# XBeeModule.net
KiCad netlist of a schematic drawn in Altium Designer
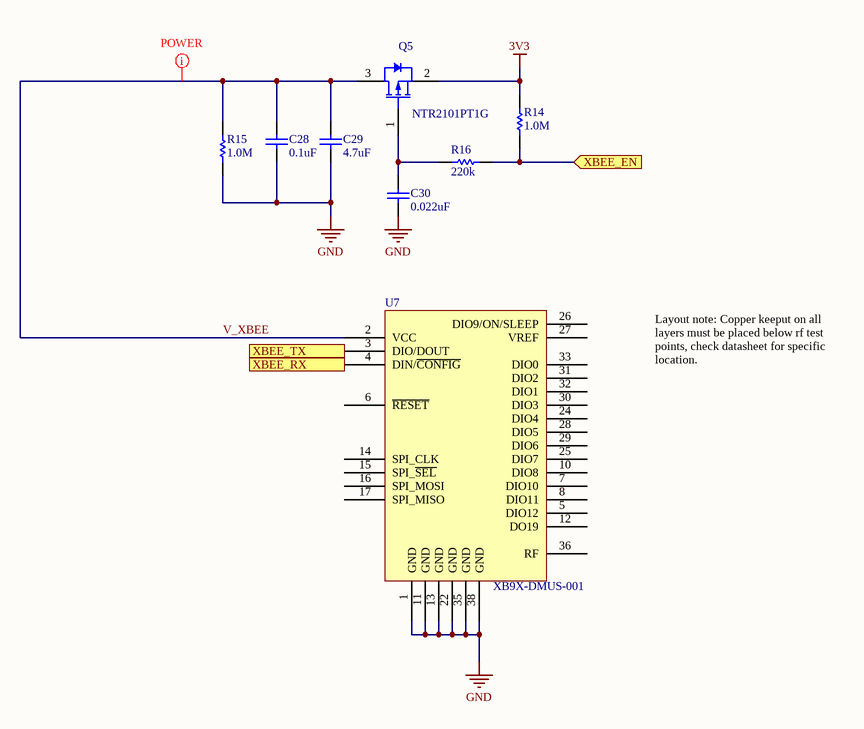
[diagram p0: XBeeModule.SchDoc]

(export (version "E")
  (design (tool "Eeschema 10.0.6"))
  (components
    (comp (ref "C28")
      (value "0.1uF")
      (footprint "0402cap")
      (description "0402 Ceramic Chip Capacitor - Standard")
      (fields (field (name "Comment") "C0402"))
      (libsource (lib "lib-Standard") (part "C0402"))
    )
    (comp (ref "C29")
      (value "4.7uF")
      (footprint "0603CAP")
      (description "0603 Ceramic Chip Capacitor - Standard")
      (fields (field (name "Comment") "C0603"))
      (libsource (lib "lib-Standard") (part "C0603"))
    )
    (comp (ref "C30")
      (value "0.022uF")
      (footprint "0402cap")
      (description "0402 Ceramic Chip Capacitor - Standard")
      (fields (field (name "Comment") "C0402"))
      (libsource (lib "lib-Standard") (part "C0402"))
    )
    (comp (ref "Q5")
      (value "NTR2101PT1G")
      (footprint "ONSC-SOT-23-3-318-08_V")
      (description "Small Signal MOSFET, -8 V, -3.7 A, Single P-Channel, 3-Pin SOT-23, Pb-Free, Tape and Reel")
      (libsource (lib "ON Semi MOSFETs") (part "NTR2101PT1G"))
    )
    (comp (ref "R14")
      (value "1.0M")
      (footprint "0402RES")
      (description "0402 Chip Resistor - Standard")
      (fields (field (name "Comment") "R0402"))
      (libsource (lib "lib-Standard") (part "R0402"))
    )
    (comp (ref "R15")
      (value "1.0M")
      (footprint "0402RES")
      (description "0402 Chip Resistor - Standard")
      (fields (field (name "Comment") "R0402"))
      (libsource (lib "lib-Standard") (part "R0402"))
    )
    (comp (ref "R16")
      (value "220k")
      (footprint "0402RES")
      (description "0402 Chip Resistor - Standard")
      (fields (field (name "Comment") "R0402"))
      (libsource (lib "lib-Standard") (part "R0402"))
    )
    (comp (ref "U7")
      (value "XB9X-DMUS-001")
      (footprint "XBee/XBee-PRO")
      (libsource (lib "lib-IC_RF") (part "XB9X-DMUS-001"))
    )
  )
  (nets
    (net (code "1") (name "/V_XBEE") (class "Default")
      (node (ref "C28") (pin "2") (pinfunction "2_2") (pintype "passive"))
      (node (ref "C29") (pin "2") (pinfunction "2_2") (pintype "passive"))
      (node (ref "Q5") (pin "3") (pinfunction "D_3") (pintype "passive"))
      (node (ref "R15") (pin "2") (pinfunction "2_2") (pintype "passive"))
      (node (ref "U7") (pin "2") (pinfunction "VCC_2") (pintype "passive"))
    )
    (net (code "2") (name "/XBEE_EN") (class "Default")
      (node (ref "R14") (pin "1") (pinfunction "1_1") (pintype "passive"))
      (node (ref "R16") (pin "2") (pinfunction "2_2") (pintype "passive"))
    )
    (net (code "3") (name "/XBEE_RX") (class "Default")
      (node (ref "U7") (pin "4") (pinfunction "DIN/~{CONFIG}_4") (pintype "passive"))
    )
    (net (code "4") (name "/XBEE_TX") (class "Default")
      (node (ref "U7") (pin "3") (pinfunction "DIO/DOUT_3") (pintype "passive"))
    )
    (net (code "5") (name "3V3") (class "Default")
      (node (ref "Q5") (pin "2") (pinfunction "S_2") (pintype "passive"))
      (node (ref "R14") (pin "2") (pinfunction "2_2") (pintype "passive"))
    )
    (net (code "6") (name "GND") (class "Default")
      (node (ref "C28") (pin "1") (pinfunction "1_1") (pintype "passive"))
      (node (ref "C29") (pin "1") (pinfunction "1_1") (pintype "passive"))
      (node (ref "C30") (pin "1") (pinfunction "1_1") (pintype "passive"))
      (node (ref "R15") (pin "1") (pinfunction "1_1") (pintype "passive"))
      (node (ref "U7") (pin "1") (pinfunction "GND_1") (pintype "passive"))
      (node (ref "U7") (pin "11") (pinfunction "GND_11") (pintype "passive"))
      (node (ref "U7") (pin "13") (pinfunction "GND_13") (pintype "passive"))
      (node (ref "U7") (pin "22") (pinfunction "GND_22") (pintype "passive"))
      (node (ref "U7") (pin "35") (pinfunction "GND_35") (pintype "passive"))
      (node (ref "U7") (pin "38") (pinfunction "GND_38") (pintype "passive"))
    )
    (net (code "7") (name "Net-(Q5-G)") (class "Default")
      (node (ref "C30") (pin "2") (pinfunction "2_2") (pintype "passive"))
      (node (ref "Q5") (pin "1") (pinfunction "G_1") (pintype "passive"))
      (node (ref "R16") (pin "1") (pinfunction "1_1") (pintype "passive"))
    )
    (net (code "8") (name "unconnected-(U7-DIO0-Pad33)") (class "Default")
      (node (ref "U7") (pin "33") (pinfunction "DIO0_33") (pintype "passive"))
    )
    (net (code "9") (name "unconnected-(U7-DIO1-Pad32)") (class "Default")
      (node (ref "U7") (pin "32") (pinfunction "DIO1_32") (pintype "passive"))
    )
    (net (code "10") (name "unconnected-(U7-DIO2-Pad31)") (class "Default")
      (node (ref "U7") (pin "31") (pinfunction "DIO2_31") (pintype "passive"))
    )
    (net (code "11") (name "unconnected-(U7-DIO3-Pad30)") (class "Default")
      (node (ref "U7") (pin "30") (pinfunction "DIO3_30") (pintype "passive"))
    )
    (net (code "12") (name "unconnected-(U7-DIO4-Pad24)") (class "Default")
      (node (ref "U7") (pin "24") (pinfunction "DIO4_24") (pintype "passive"))
    )
    (net (code "13") (name "unconnected-(U7-DIO5-Pad28)") (class "Default")
      (node (ref "U7") (pin "28") (pinfunction "DIO5_28") (pintype "passive"))
    )
    (net (code "14") (name "unconnected-(U7-DIO6-Pad29)") (class "Default")
      (node (ref "U7") (pin "29") (pinfunction "DIO6_29") (pintype "passive"))
    )
    (net (code "15") (name "unconnected-(U7-DIO7-Pad25)") (class "Default")
      (node (ref "U7") (pin "25") (pinfunction "DIO7_25") (pintype "passive"))
    )
    (net (code "16") (name "unconnected-(U7-DIO8-Pad10)") (class "Default")
      (node (ref "U7") (pin "10") (pinfunction "DIO8_10") (pintype "passive"))
    )
    (net (code "17") (name "unconnected-(U7-DIO9{slash}ON{slash}SLEEP-Pad26)") (class "Default")
      (node (ref "U7") (pin "26") (pinfunction "DIO9/ON/SLEEP_26") (pintype "passive"))
    )
    (net (code "18") (name "unconnected-(U7-DIO10-Pad7)") (class "Default")
      (node (ref "U7") (pin "7") (pinfunction "DIO10_7") (pintype "passive"))
    )
    (net (code "19") (name "unconnected-(U7-DIO11-Pad8)") (class "Default")
      (node (ref "U7") (pin "8") (pinfunction "DIO11_8") (pintype "passive"))
    )
    (net (code "20") (name "unconnected-(U7-DIO12-Pad5)") (class "Default")
      (node (ref "U7") (pin "5") (pinfunction "DIO12_5") (pintype "passive"))
    )
    (net (code "21") (name "unconnected-(U7-DO19-Pad12)") (class "Default")
      (node (ref "U7") (pin "12") (pinfunction "DO19_12") (pintype "passive"))
    )
    (net (code "22") (name "unconnected-(U7-RF-Pad36)") (class "Default")
      (node (ref "U7") (pin "36") (pinfunction "RF_36") (pintype "passive"))
    )
    (net (code "23") (name "unconnected-(U7-SPI_CLK-Pad14)") (class "Default")
      (node (ref "U7") (pin "14") (pinfunction "SPI_CLK_14") (pintype "passive"))
    )
    (net (code "24") (name "unconnected-(U7-SPI_MISO-Pad17)") (class "Default")
      (node (ref "U7") (pin "17") (pinfunction "SPI_MISO_17") (pintype "passive"))
    )
    (net (code "25") (name "unconnected-(U7-SPI_MOSI-Pad16)") (class "Default")
      (node (ref "U7") (pin "16") (pinfunction "SPI_MOSI_16") (pintype "passive"))
    )
    (net (code "26") (name "unconnected-(U7-SPI_~{SEL}-Pad15)") (class "Default")
      (node (ref "U7") (pin "15") (pinfunction "SPI_~{SEL}_15") (pintype "passive"))
    )
    (net (code "27") (name "unconnected-(U7-VREF-Pad27)") (class "Default")
      (node (ref "U7") (pin "27") (pinfunction "VREF_27") (pintype "passive"))
    )
    (net (code "28") (name "unconnected-(U7-~{RESET}-Pad6)") (class "Default")
      (node (ref "U7") (pin "6") (pinfunction "~{RESET}_6") (pintype "passive"))
    )
  )
)
